# Sheet1.net
KiCad netlist of a schematic drawn in Altium Designer
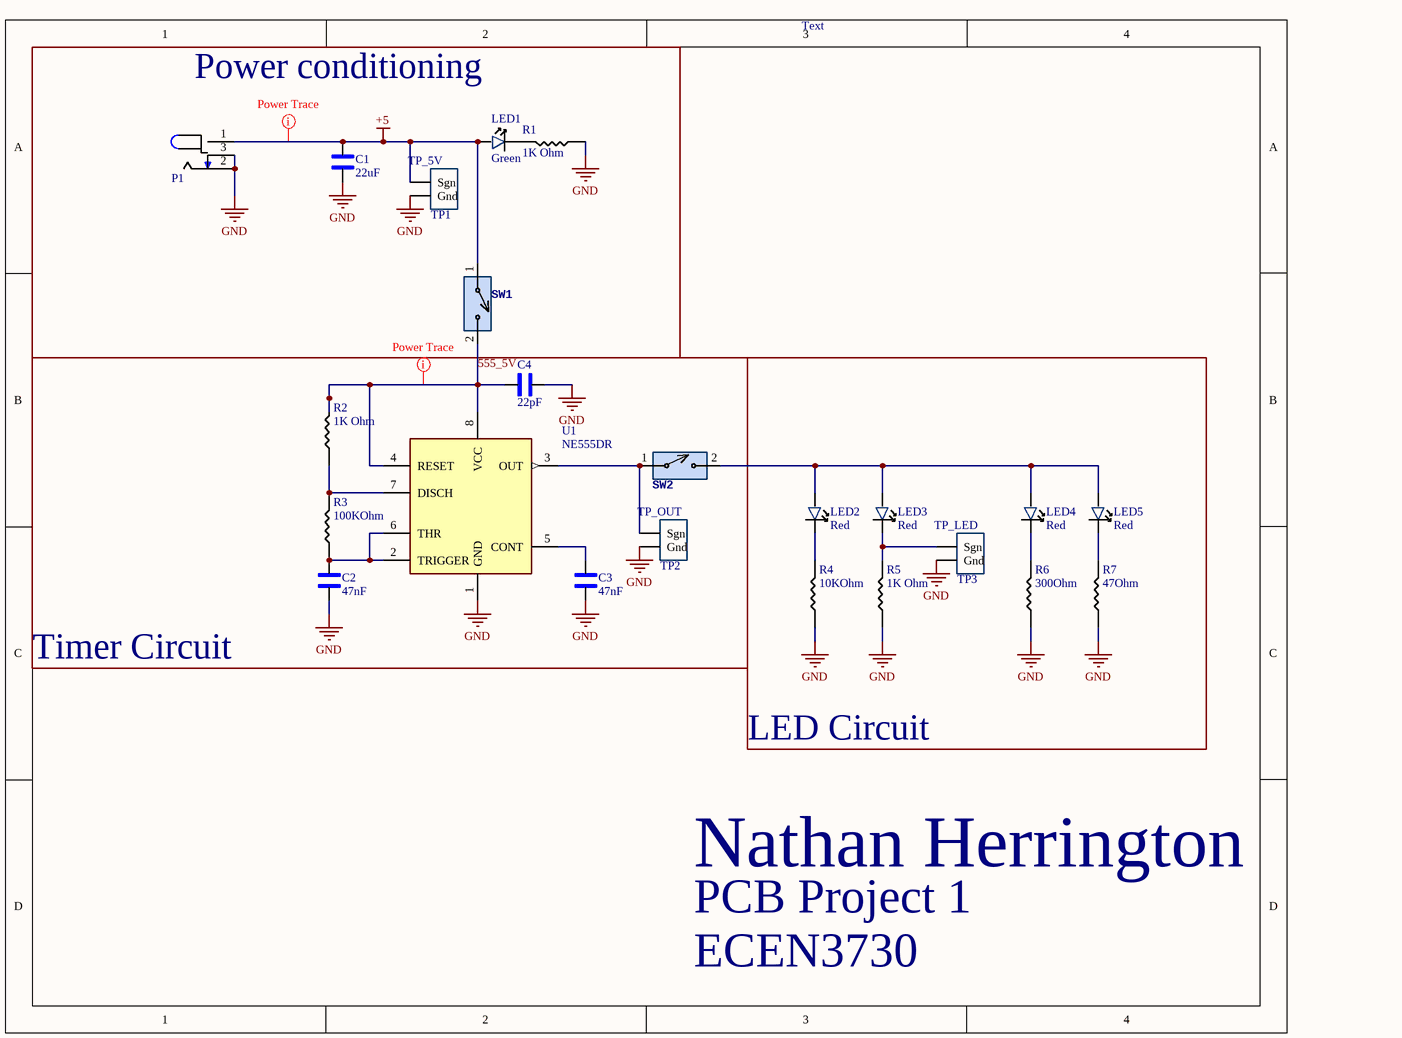
[diagram p0: Sheet1.SchDoc]

(export (version "E")
  (design (tool "Eeschema 10.0.6"))
  (components
    (comp (ref "C1")
      (value "22uF")
      (footprint "1206_Passive_Capacitor")
      (description "22uF ±10% 25V X5R 1206 Multilayer Ceramic Capacitors MLCC - SMD/SMT RoHS")
      (fields (field (name "MFR PART #") "CL31A226KAHNNNE") (field (name "LCSC PART#") "C12891"))
      (libsource (lib "ECEN5730Lib_2023_05_DS") (part "C_22uF_1206"))
    )
    (comp (ref "C2")
      (value "47nF")
      (footprint "1206_Passive_Capacitor")
      (description "47nF ±5% 50V C0G 1206 Multilayer Ceramic Capacitors MLCC - SMD/SMT RoHS")
      (fields (field (name "LCSC PART#") "C21812") (field (name "MFR PART #") "GRM31M5C1H473JA01L"))
      (libsource (lib "ECEN5730Lib_2023_05_DS") (part "C_47nF_1206"))
    )
    (comp (ref "C3")
      (value "47nF")
      (footprint "1206_Passive_Capacitor")
      (description "47nF ±5% 50V C0G 1206 Multilayer Ceramic Capacitors MLCC - SMD/SMT RoHS")
      (fields (field (name "LCSC PART#") "C21812") (field (name "MFR PART #") "GRM31M5C1H473JA01L"))
      (libsource (lib "ECEN5730Lib_2023_05_DS") (part "C_47nF_1206"))
    )
    (comp (ref "C4")
      (value "22pF")
      (footprint "1206_Passive_Capacitor")
      (description "22pF ±5% 1kV C0G 1206 Multilayer Ceramic Capacitors MLCC - SMD/SMT RoHS")
      (fields (field (name "LCSC PART#") "C107174") (field (name "MFR PART #") "CC1206JKNPOCBN220"))
      (libsource (lib "ECEN5730Lib_2023_05_DS") (part "C_22pF_1206"))
    )
    (comp (ref "LED1")
      (value "Green")
      (footprint "LED_1206")
      (description "Green 513~528nm 1206 Light Emitting Diodes (LED) RoHS")
      (fields (field (name "MFR PART #") "SZYY1206G") (field (name "LCSC PART#") "C434439"))
      (libsource (lib "ECEN5730Lib_2023_05_DS") (part "LED_GREEN_1206"))
    )
    (comp (ref "LED2")
      (value "Red")
      (footprint "LED_1206")
      (description "Red 621~631nm 1206 Light Emitting Diodes (LED) RoHS")
      (fields (field (name "MFR PART #") "15-21/R6C-FQ1R1B/2T") (field (name "LCSC PART#") "C93133"))
      (libsource (lib "ECEN5730Lib_2023_05_DS") (part "LED_RED_1206"))
    )
    (comp (ref "LED3")
      (value "Red")
      (footprint "LED_1206")
      (description "Red 621~631nm 1206 Light Emitting Diodes (LED) RoHS")
      (fields (field (name "MFR PART #") "15-21/R6C-FQ1R1B/2T") (field (name "LCSC PART#") "C93133"))
      (libsource (lib "ECEN5730Lib_2023_05_DS") (part "LED_RED_1206"))
    )
    (comp (ref "LED4")
      (value "Red")
      (footprint "LED_1206")
      (description "Red 621~631nm 1206 Light Emitting Diodes (LED) RoHS")
      (fields (field (name "MFR PART #") "15-21/R6C-FQ1R1B/2T") (field (name "LCSC PART#") "C93133"))
      (libsource (lib "ECEN5730Lib_2023_05_DS") (part "LED_RED_1206"))
    )
    (comp (ref "LED5")
      (value "Red")
      (footprint "LED_1206")
      (description "Red 621~631nm 1206 Light Emitting Diodes (LED) RoHS")
      (fields (field (name "MFR PART #") "15-21/R6C-FQ1R1B/2T") (field (name "LCSC PART#") "C93133"))
      (libsource (lib "ECEN5730Lib_2023_05_DS") (part "LED_RED_1206"))
    )
    (comp (ref "P1")
      (value "Power Jack")
      (footprint "Power_Jack")
      (description "Power Barrel Connector Jack 2.10mm ID (0.083\"), 5.50mm OD (0.217\") Through Hole, Right Angle")
      (fields (field (name "MFR PART #") "PJ-102A") (field (name "LCSC PART#") "C136744"))
      (libsource (lib "ECEN5730Lib_2023_05_DS") (part "P_Power Jack"))
    )
    (comp (ref "R1")
      (value "1K Ohm")
      (footprint "1206_Passive_Resitor")
      (description "CHIP RESISTOR - SURFACE MOUNT 1KOHMS ±1% 1/4W 1206 ROHS")
      (fields (field (name "MFR PART #") "RNCP1206FTD1K00CT") (field (name "LCSC PART#") "C4410"))
      (libsource (lib "ECEN5730Lib_2023_05_DS") (part "R_1K_1206"))
    )
    (comp (ref "R2")
      (value "1K Ohm")
      (footprint "1206_Passive_Resitor")
      (description "CHIP RESISTOR - SURFACE MOUNT 1KOHMS ±1% 1/4W 1206 ROHS")
      (fields (field (name "MFR PART #") "RNCP1206FTD1K00CT") (field (name "LCSC PART#") "C4410"))
      (libsource (lib "ECEN5730Lib_2023_05_DS") (part "R_1K_1206"))
    )
    (comp (ref "R3")
      (value "100KOhm")
      (footprint "1206_Passive_Resitor")
      (description "100kΩ ±1% 0.25W ±100ppm/℃ 1206 Chip Resistor - Surface Mount RoHS")
      (fields (field (name "LCSC PART#") "C17900") (field (name "MFR PART #") "1206W4F1003T5E"))
      (libsource (lib "ECEN5730Lib_2023_05_DS") (part "R_100KOhm_1206"))
    )
    (comp (ref "R4")
      (value "10KOhm")
      (footprint "1206_Passive_Resitor")
      (description "10 kOhms ±5% 0.25W, 1/4W Chip Resistor 1206 (3216 Metric) Automotive AEC-Q200 Thick Film")
      (fields (field (name "MFR PART #") "RMCF1206FT10K0") (field (name "LCSC PART#") "C17902"))
      (libsource (lib "ECEN5730Lib_2023_05_DS") (part "R_10KOhm_1206"))
    )
    (comp (ref "R5")
      (value "1K Ohm")
      (footprint "1206_Passive_Resitor")
      (description "CHIP RESISTOR - SURFACE MOUNT 1KOHMS ±1% 1/4W 1206 ROHS")
      (fields (field (name "MFR PART #") "RNCP1206FTD1K00CT") (field (name "LCSC PART#") "C4410"))
      (libsource (lib "ECEN5730Lib_2023_05_DS") (part "R_1K_1206"))
    )
    (comp (ref "R6")
      (value "300Ohm")
      (footprint "1206_Passive_Resitor")
      (description "CHIP RESISTOR - SURFACE MOUNT 300OHMS ±1% 1/4W 1206 ROHS")
      (fields (field (name "MFR PART #") "1206W4F3000T5E") (field (name "LCSC PART#") "C17887"))
      (libsource (lib "ECEN5730Lib_2023_05_DS") (part "R_300Ohm_1206"))
    )
    (comp (ref "R7")
      (value "47Ohm")
      (footprint "1206_Passive_Resitor")
      (description "47Ω ±5% 0.25W ±200ppm/℃ 1206 Chip Resistor - Surface Mount RoHS")
      (fields (field (name "MFR PART #") "1206W4J0470T5E") (field (name "LCSC PART#") "C25384"))
      (libsource (lib "ECEN5730Lib_2023_05_DS") (part "R_47Ohm_1206"))
    )
    (comp (ref "SW1")
      (value "SW_2Pin_100mil_Switch")
      (footprint "2Pin-Header-Conn")
      (description "2Pin Header")
      (fields (field (name "LCSC PART#") "C124375"))
      (libsource (lib "ECEN5730Lib_2023_05_DS") (part "SW_2Pin_100mil_Switch"))
    )
    (comp (ref "SW2")
      (value "SW_2Pin_100mil_Switch")
      (footprint "2Pin-Header-Conn")
      (description "2Pin Header")
      (fields (field (name "LCSC PART#") "C124375"))
      (libsource (lib "") (part "SW_2Pin_100mil_Switch_1"))
    )
    (comp (ref "TP1")
      (value "TP_5V")
      (footprint "TP10x_Probe")
      (description "Test Point 300 mil centers")
      (libsource (lib "ECEN5730Lib_2023_05_DS") (part "TP_10x_Probe"))
    )
    (comp (ref "TP2")
      (value "TP_OUT")
      (footprint "TP10x_Probe")
      (description "Test Point 300 mil centers")
      (libsource (lib "ECEN5730Lib_2023_05_DS") (part "TP_10x_Probe"))
    )
    (comp (ref "TP3")
      (value "TP_LED")
      (footprint "TP10x_Probe")
      (description "Test Point 300 mil centers")
      (libsource (lib "ECEN5730Lib_2023_05_DS") (part "TP_10x_Probe"))
    )
    (comp (ref "U1")
      (value "NE555DR")
      (footprint "TS555IDTTR")
      (description "555 Timer SOIC-8_150MIL ROHS 150ns Rise Time")
      (fields (field (name "LCSC PART#") "C7593"))
      (libsource (lib "ECEN5730Lib_2023_05_DS") (part "U_555_Slow"))
    )
  )
  (nets
    (net (code "1") (name "+5") (class "Default")
      (node (ref "C1") (pin "2") (pinfunction "2_2") (pintype "passive"))
      (node (ref "LED1") (pin "1") (pinfunction "1_1") (pintype "passive"))
      (node (ref "P1") (pin "1") (pinfunction "1_1") (pintype "power_in"))
      (node (ref "SW1") (pin "1") (pinfunction "1_1") (pintype "passive"))
      (node (ref "TP1") (pin "1") (pinfunction "Sgn_1") (pintype "passive"))
    )
    (net (code "2") (name "/555_5V") (class "Default")
      (node (ref "C4") (pin "2") (pinfunction "2_2") (pintype "passive"))
      (node (ref "R2") (pin "2") (pinfunction "2_2") (pintype "passive"))
      (node (ref "SW1") (pin "2") (pinfunction "2_2") (pintype "passive"))
      (node (ref "U1") (pin "4") (pinfunction "RESET_4") (pintype "passive"))
      (node (ref "U1") (pin "8") (pinfunction "VCC_8") (pintype "power_in"))
    )
    (net (code "3") (name "GND") (class "Default")
      (node (ref "C1") (pin "1") (pinfunction "1_1") (pintype "passive"))
      (node (ref "C2") (pin "1") (pinfunction "1_1") (pintype "passive"))
      (node (ref "C3") (pin "1") (pinfunction "1_1") (pintype "passive"))
      (node (ref "C4") (pin "1") (pinfunction "1_1") (pintype "passive"))
      (node (ref "P1") (pin "2") (pinfunction "2_2") (pintype "power_in"))
      (node (ref "P1") (pin "3") (pinfunction "3_3") (pintype "power_in"))
      (node (ref "R1") (pin "1") (pinfunction "1_1") (pintype "passive"))
      (node (ref "R4") (pin "1") (pinfunction "1_1") (pintype "passive"))
      (node (ref "R5") (pin "1") (pinfunction "1_1") (pintype "passive"))
      (node (ref "R6") (pin "1") (pinfunction "1_1") (pintype "passive"))
      (node (ref "R7") (pin "1") (pinfunction "1_1") (pintype "passive"))
      (node (ref "TP1") (pin "2") (pinfunction "Gnd_2") (pintype "passive"))
      (node (ref "TP2") (pin "2") (pinfunction "Gnd_2") (pintype "passive"))
      (node (ref "TP3") (pin "2") (pinfunction "Gnd_2") (pintype "passive"))
      (node (ref "U1") (pin "1") (pinfunction "GND_1") (pintype "power_in"))
    )
    (net (code "4") (name "Net-(LED1-Pad2)") (class "Default")
      (node (ref "LED1") (pin "2") (pinfunction "2_2") (pintype "passive"))
      (node (ref "R1") (pin "2") (pinfunction "2_2") (pintype "passive"))
    )
    (net (code "5") (name "Net-(LED2-Pad1)") (class "Default")
      (node (ref "LED2") (pin "1") (pinfunction "1_1") (pintype "passive"))
      (node (ref "LED3") (pin "1") (pinfunction "1_1") (pintype "passive"))
      (node (ref "LED4") (pin "1") (pinfunction "1_1") (pintype "passive"))
      (node (ref "LED5") (pin "1") (pinfunction "1_1") (pintype "passive"))
      (node (ref "SW2") (pin "2") (pinfunction "2_2") (pintype "passive"))
    )
    (net (code "6") (name "Net-(LED2-Pad2)") (class "Default")
      (node (ref "LED2") (pin "2") (pinfunction "2_2") (pintype "passive"))
      (node (ref "R4") (pin "2") (pinfunction "2_2") (pintype "passive"))
    )
    (net (code "7") (name "Net-(LED4-Pad2)") (class "Default")
      (node (ref "LED4") (pin "2") (pinfunction "2_2") (pintype "passive"))
      (node (ref "R6") (pin "2") (pinfunction "2_2") (pintype "passive"))
    )
    (net (code "8") (name "Net-(LED5-Pad2)") (class "Default")
      (node (ref "LED5") (pin "2") (pinfunction "2_2") (pintype "passive"))
      (node (ref "R7") (pin "2") (pinfunction "2_2") (pintype "passive"))
    )
    (net (code "9") (name "Net-(TP2-Sgn)") (class "Default")
      (node (ref "SW2") (pin "1") (pinfunction "1_1") (pintype "passive"))
      (node (ref "TP2") (pin "1") (pinfunction "Sgn_1") (pintype "passive"))
      (node (ref "U1") (pin "3") (pinfunction "OUT_3") (pintype "output"))
    )
    (net (code "10") (name "Net-(TP3-Sgn)") (class "Default")
      (node (ref "LED3") (pin "2") (pinfunction "2_2") (pintype "passive"))
      (node (ref "R5") (pin "2") (pinfunction "2_2") (pintype "passive"))
      (node (ref "TP3") (pin "1") (pinfunction "Sgn_1") (pintype "passive"))
    )
    (net (code "11") (name "Net-(U1-CONT)") (class "Default")
      (node (ref "C3") (pin "2") (pinfunction "2_2") (pintype "passive"))
      (node (ref "U1") (pin "5") (pinfunction "CONT_5") (pintype "passive"))
    )
    (net (code "12") (name "Net-(U1-DISCH)") (class "Default")
      (node (ref "R2") (pin "1") (pinfunction "1_1") (pintype "passive"))
      (node (ref "R3") (pin "2") (pinfunction "2_2") (pintype "passive"))
      (node (ref "U1") (pin "7") (pinfunction "DISCH_7") (pintype "passive"))
    )
    (net (code "13") (name "Net-(U1-THR)") (class "Default")
      (node (ref "C2") (pin "2") (pinfunction "2_2") (pintype "passive"))
      (node (ref "R3") (pin "1") (pinfunction "1_1") (pintype "passive"))
      (node (ref "U1") (pin "2") (pinfunction "TRIGGER_2") (pintype "passive"))
      (node (ref "U1") (pin "6") (pinfunction "THR_6") (pintype "passive"))
    )
  )
)
